# Controls_Architecture.net
KiCad netlist of a schematic drawn in Altium Designer
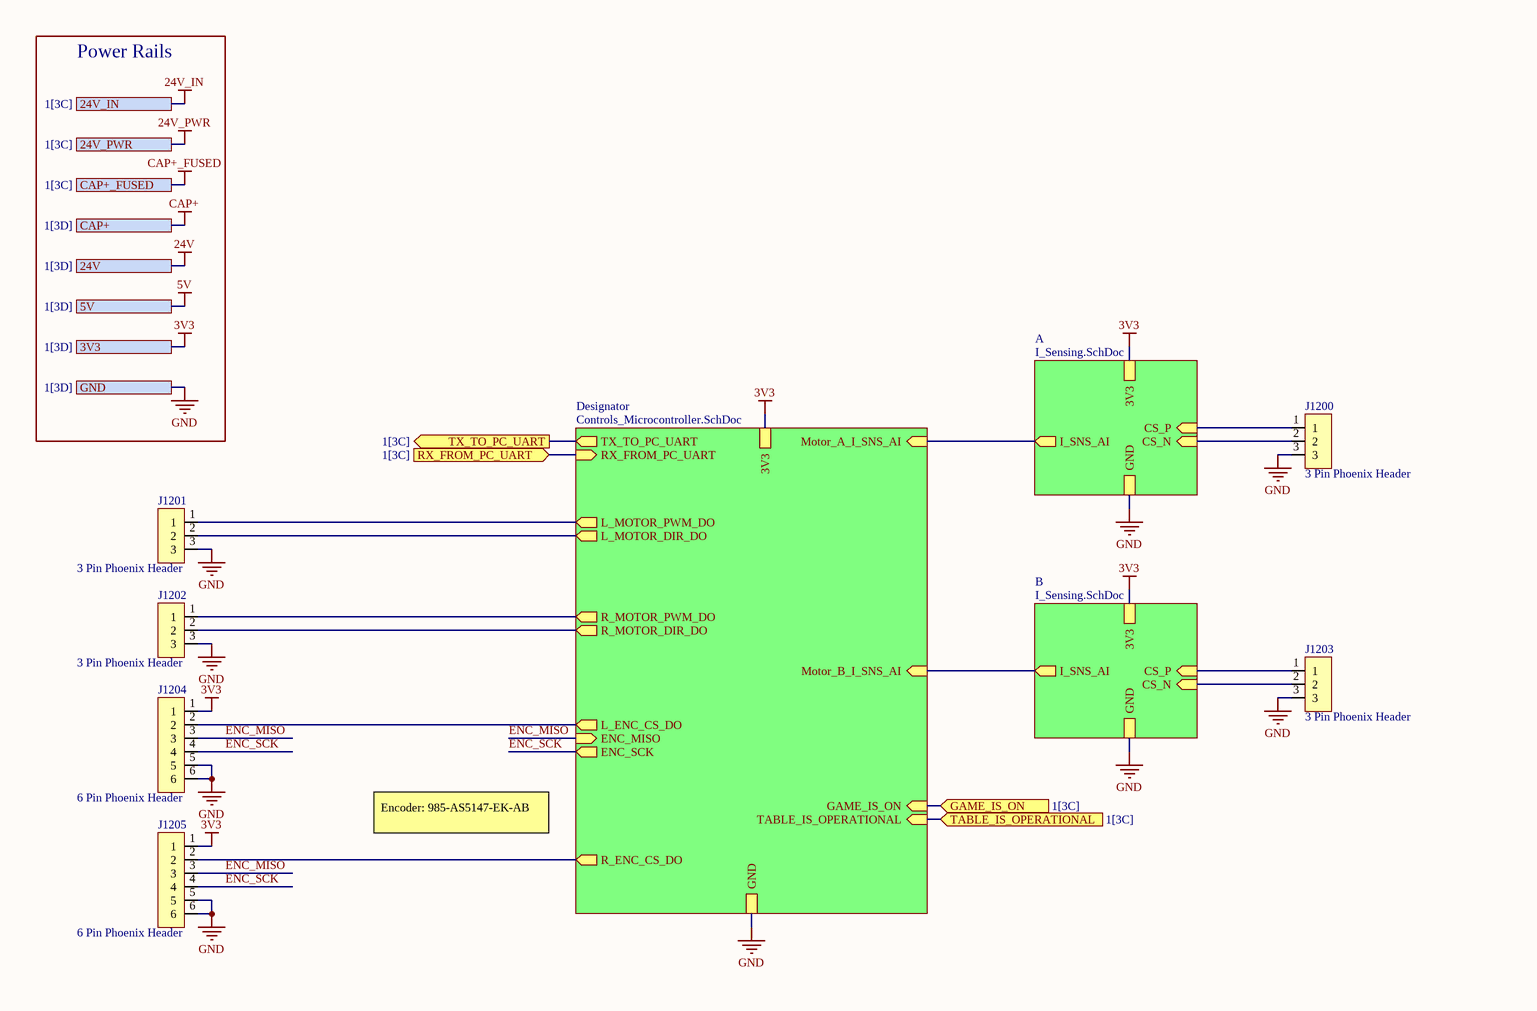
[diagram p0: Controls_Architecture.SchDoc, left]
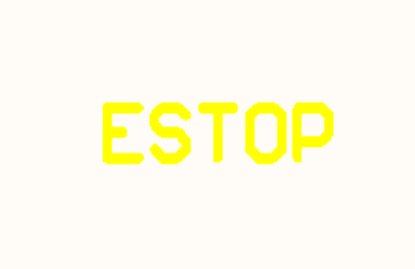
[diagram p1: Controls_Architecture.SchDoc, right]

(export (version "E")
  (design (tool "Eeschema 10.0.6"))
  (components
    (comp (ref "J1200")
      (value "3 Pin Phoenix Header")
      (footprint "3 Pin Phoenix Header")
      (libsource (lib "") (part "3 Pin Phoenix Header_1"))
    )
    (comp (ref "J1201")
      (value "3 Pin Phoenix Header")
      (footprint "3 Pin Phoenix Header")
      (libsource (lib "air_hockey_lib") (part "3 Pin Phoenix Header"))
    )
    (comp (ref "J1202")
      (value "3 Pin Phoenix Header")
      (footprint "3 Pin Phoenix Header")
      (libsource (lib "air_hockey_lib") (part "3 Pin Phoenix Header"))
    )
    (comp (ref "J1203")
      (value "3 Pin Phoenix Header")
      (footprint "3 Pin Phoenix Header")
      (libsource (lib "") (part "3 Pin Phoenix Header_1"))
    )
    (comp (ref "J1204")
      (value "6 Pin Phoenix Header")
      (footprint "6 Pin Phoenix Header")
      (libsource (lib "air_hockey_lib") (part "6 Pin Phoenix Header"))
    )
    (comp (ref "J1205")
      (value "6 Pin Phoenix Header")
      (footprint "6 Pin Phoenix Header")
      (libsource (lib "air_hockey_lib") (part "6 Pin Phoenix Header"))
    )
  )
  (nets
    (net (code "1") (name "/CS_N") (class "Default")
      (node (ref "J1200") (pin "2") (pinfunction "2_2") (pintype "passive"))
    )
    (net (code "2") (name "/CS_N_1") (class "Default")
      (node (ref "J1203") (pin "2") (pinfunction "2_2") (pintype "passive"))
    )
    (net (code "3") (name "/CS_P") (class "Default")
      (node (ref "J1200") (pin "1") (pinfunction "1_1") (pintype "passive"))
    )
    (net (code "4") (name "/CS_P_1") (class "Default")
      (node (ref "J1203") (pin "1") (pinfunction "1_1") (pintype "passive"))
    )
    (net (code "5") (name "/ENC_MISO") (class "Default")
      (node (ref "J1204") (pin "3") (pinfunction "3_3") (pintype "passive"))
      (node (ref "J1205") (pin "3") (pinfunction "3_3") (pintype "passive"))
    )
    (net (code "6") (name "/ENC_SCK") (class "Default")
      (node (ref "J1204") (pin "4") (pinfunction "4_4") (pintype "passive"))
      (node (ref "J1205") (pin "4") (pinfunction "4_4") (pintype "passive"))
    )
    (net (code "10") (name "/L_ENC_CS_DO") (class "Default")
      (node (ref "J1204") (pin "2") (pinfunction "2_2") (pintype "passive"))
    )
    (net (code "11") (name "/L_MOTOR_DIR_DO") (class "Default")
      (node (ref "J1201") (pin "2") (pinfunction "2_2") (pintype "passive"))
    )
    (net (code "12") (name "/L_MOTOR_PWM_DO") (class "Default")
      (node (ref "J1201") (pin "1") (pinfunction "1_1") (pintype "passive"))
    )
    (net (code "14") (name "/R_ENC_CS_DO") (class "Default")
      (node (ref "J1205") (pin "2") (pinfunction "2_2") (pintype "passive"))
    )
    (net (code "15") (name "/R_MOTOR_DIR_DO") (class "Default")
      (node (ref "J1202") (pin "2") (pinfunction "2_2") (pintype "passive"))
    )
    (net (code "16") (name "/R_MOTOR_PWM_DO") (class "Default")
      (node (ref "J1202") (pin "1") (pinfunction "1_1") (pintype "passive"))
    )
    (net (code "19") (name "3V3") (class "Default")
      (node (ref "J1204") (pin "1") (pinfunction "1_1") (pintype "passive"))
      (node (ref "J1205") (pin "1") (pinfunction "1_1") (pintype "passive"))
    )
    (net (code "26") (name "GND") (class "Default")
      (node (ref "J1200") (pin "3") (pinfunction "3_3") (pintype "passive"))
      (node (ref "J1201") (pin "3") (pinfunction "3_3") (pintype "passive"))
      (node (ref "J1202") (pin "3") (pinfunction "3_3") (pintype "passive"))
      (node (ref "J1203") (pin "3") (pinfunction "3_3") (pintype "passive"))
      (node (ref "J1204") (pin "5") (pinfunction "5_5") (pintype "passive"))
      (node (ref "J1204") (pin "6") (pinfunction "6_6") (pintype "passive"))
      (node (ref "J1205") (pin "5") (pinfunction "5_5") (pintype "passive"))
      (node (ref "J1205") (pin "6") (pinfunction "6_6") (pintype "passive"))
    )
  )
)
